# PIC32MX250F128B.net
KiCad netlist of a schematic drawn in EAGLE
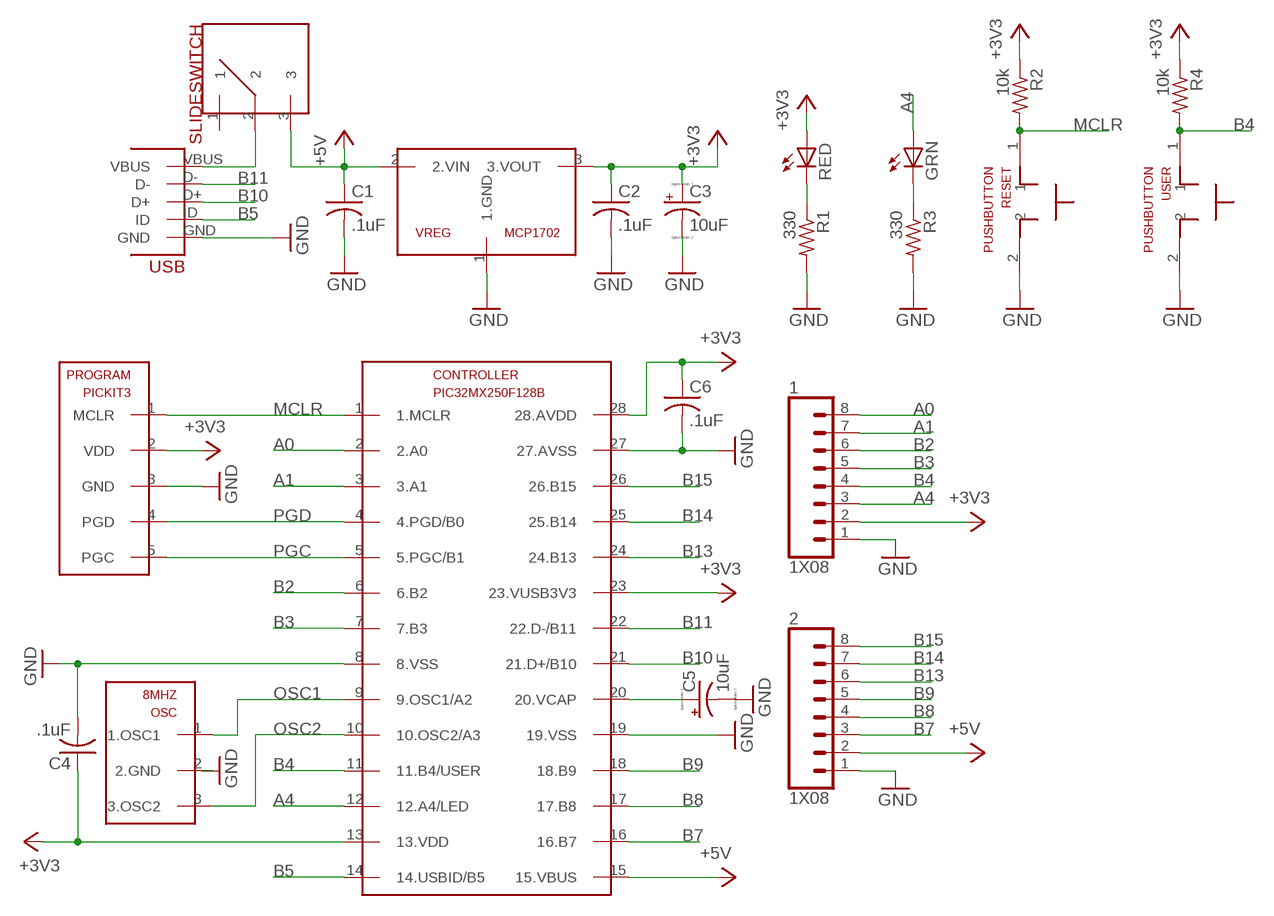
[diagram p0: schematic, sheet 1]

(export (version "E")
  (design (tool "Eeschema 10.0.6"))
  (components
    (comp (ref "1")
      (value "1X08")
      (footprint "eagle-import:CONN_08")
      (libsource (lib "eagle-import") (part "1X08"))
    )
    (comp (ref "2")
      (value "1X08")
      (footprint "eagle-import:CONN_08")
      (libsource (lib "eagle-import") (part "1X08"))
    )
    (comp (ref "8MHZ")
      (value "OSC")
      (footprint "eagle-import:OSC")
      (libsource (lib "eagle-import") (part "OSC"))
    )
    (comp (ref "C1")
      (value ".1uF")
      (footprint "eagle-import:C025-025X050")
      (libsource (lib "eagle-import") (part "C-US025-025X050"))
    )
    (comp (ref "C2")
      (value ".1uF")
      (footprint "eagle-import:C025-025X050")
      (libsource (lib "eagle-import") (part "C-US025-025X050"))
    )
    (comp (ref "C3")
      (value "10uF")
      (footprint "eagle-import:B45181B")
      (libsource (lib "eagle-import") (part "CPOL-USB45181B"))
    )
    (comp (ref "C4")
      (value ".1uF")
      (footprint "eagle-import:C025-025X050")
      (libsource (lib "eagle-import") (part "C-US025-025X050"))
    )
    (comp (ref "C5")
      (value "10uF")
      (footprint "eagle-import:B45181B")
      (libsource (lib "eagle-import") (part "CPOL-USB45181B"))
    )
    (comp (ref "C6")
      (value ".1uF")
      (footprint "eagle-import:C025-025X050")
      (libsource (lib "eagle-import") (part "C-US025-025X050"))
    )
    (comp (ref "CONTROLLER")
      (value "PIC32MX250F128B")
      (footprint "eagle-import:DIL28-3")
      (libsource (lib "eagle-import") (part "PIC32MX250F128B"))
    )
    (comp (ref "GRN")
      (value "LED3MM")
      (footprint "eagle-import:LED3MM")
      (libsource (lib "eagle-import") (part "LED3MM"))
    )
    (comp (ref "PROGRAM")
      (value "PICKIT3")
      (footprint "eagle-import:PICKIT3")
      (libsource (lib "eagle-import") (part "PICKIT3"))
    )
    (comp (ref "R1")
      (value "330")
      (footprint "eagle-import:0207_10")
      (libsource (lib "eagle-import") (part "R-US_0207/10"))
    )
    (comp (ref "R2")
      (value "10k")
      (footprint "eagle-import:0207_10")
      (libsource (lib "eagle-import") (part "R-US_0207/10"))
    )
    (comp (ref "R3")
      (value "330")
      (footprint "eagle-import:0207_10")
      (libsource (lib "eagle-import") (part "R-US_0207/10"))
    )
    (comp (ref "R4")
      (value "10k")
      (footprint "eagle-import:0207_10")
      (libsource (lib "eagle-import") (part "R-US_0207/10"))
    )
    (comp (ref "RED")
      (value "LED3MM")
      (footprint "eagle-import:LED3MM")
      (libsource (lib "eagle-import") (part "LED3MM"))
    )
    (comp (ref "RESET")
      (value "PUSHBUTTON")
      (footprint "eagle-import:PUSHBUTTON")
      (libsource (lib "eagle-import") (part "PUSHBUTTON"))
    )
    (comp (ref "SLIDESWITCH")
      (value "SLIDESWITCH")
      (footprint "eagle-import:SLIDESWITCH")
      (libsource (lib "eagle-import") (part "SLIDESWITCH"))
    )
    (comp (ref "USB")
      (value "MINIUSB")
      (footprint "eagle-import:USB-MB-H")
      (libsource (lib "eagle-import") (part "MINIUSB"))
    )
    (comp (ref "USER")
      (value "PUSHBUTTON")
      (footprint "eagle-import:PUSHBUTTON")
      (libsource (lib "eagle-import") (part "PUSHBUTTON"))
    )
    (comp (ref "VREG")
      (value "MCP1702")
      (footprint "eagle-import:TO92")
      (libsource (lib "eagle-import") (part "MCP1702"))
    )
  )
  (nets
    (net (code "1") (name "+3V3") (class "Default")
      (node (ref "1") (pin "2") (pinfunction "2_2") (pintype "passive"))
      (node (ref "C2") (pin "1") (pinfunction "1_1") (pintype "passive"))
      (node (ref "C3") (pin "+") (pinfunction "+_+") (pintype "passive"))
      (node (ref "C4") (pin "1") (pinfunction "1_1") (pintype "passive"))
      (node (ref "C6") (pin "1") (pinfunction "1_1") (pintype "passive"))
      (node (ref "CONTROLLER") (pin "13") (pinfunction "13.VDD_13") (pintype "bidirectional"))
      (node (ref "CONTROLLER") (pin "23") (pinfunction "23.VUSB3V3_23") (pintype "bidirectional"))
      (node (ref "CONTROLLER") (pin "28") (pinfunction "28.AVDD_28") (pintype "bidirectional"))
      (node (ref "PROGRAM") (pin "2") (pinfunction "VDD_2") (pintype "bidirectional"))
      (node (ref "R2") (pin "1") (pinfunction "1_1") (pintype "passive"))
      (node (ref "R4") (pin "1") (pinfunction "1_1") (pintype "passive"))
      (node (ref "RED") (pin "A") (pinfunction "A_A") (pintype "passive"))
      (node (ref "VREG") (pin "3") (pinfunction "3.VOUT_3") (pintype "bidirectional"))
    )
    (net (code "2") (name "+5V") (class "Default")
      (node (ref "2") (pin "2") (pinfunction "2_2") (pintype "passive"))
      (node (ref "C1") (pin "1") (pinfunction "1_1") (pintype "passive"))
      (node (ref "CONTROLLER") (pin "15") (pinfunction "15.VBUS_15") (pintype "bidirectional"))
      (node (ref "SLIDESWITCH") (pin "3") (pinfunction "3_3") (pintype "bidirectional"))
      (node (ref "VREG") (pin "2") (pinfunction "2.VIN_2") (pintype "bidirectional"))
    )
    (net (code "3") (name "/A0") (class "Default")
      (node (ref "1") (pin "8") (pinfunction "8_8") (pintype "passive"))
      (node (ref "CONTROLLER") (pin "2") (pinfunction "2.A0_2") (pintype "bidirectional"))
    )
    (net (code "4") (name "/A1") (class "Default")
      (node (ref "1") (pin "7") (pinfunction "7_7") (pintype "passive"))
      (node (ref "CONTROLLER") (pin "3") (pinfunction "3.A1_3") (pintype "bidirectional"))
    )
    (net (code "5") (name "/A4") (class "Default")
      (node (ref "1") (pin "3") (pinfunction "3_3") (pintype "passive"))
      (node (ref "CONTROLLER") (pin "12") (pinfunction "12.A4/LED_12") (pintype "bidirectional"))
      (node (ref "GRN") (pin "A") (pinfunction "A_A") (pintype "passive"))
    )
    (net (code "6") (name "/B2") (class "Default")
      (node (ref "1") (pin "6") (pinfunction "6_6") (pintype "passive"))
      (node (ref "CONTROLLER") (pin "6") (pinfunction "6.B2_6") (pintype "bidirectional"))
    )
    (net (code "7") (name "/B3") (class "Default")
      (node (ref "1") (pin "5") (pinfunction "5_5") (pintype "passive"))
      (node (ref "CONTROLLER") (pin "7") (pinfunction "7.B3_7") (pintype "bidirectional"))
    )
    (net (code "8") (name "/B4") (class "Default")
      (node (ref "1") (pin "4") (pinfunction "4_4") (pintype "passive"))
      (node (ref "CONTROLLER") (pin "11") (pinfunction "11.B4/USER_11") (pintype "bidirectional"))
      (node (ref "R4") (pin "2") (pinfunction "2_2") (pintype "passive"))
      (node (ref "USER") (pin "1") (pinfunction "1_1") (pintype "bidirectional"))
    )
    (net (code "9") (name "/B5") (class "Default")
      (node (ref "CONTROLLER") (pin "14") (pinfunction "14.USBID/B5_14") (pintype "bidirectional"))
      (node (ref "USB") (pin "ID") (pinfunction "ID_ID") (pintype "bidirectional"))
    )
    (net (code "10") (name "/B7") (class "Default")
      (node (ref "2") (pin "3") (pinfunction "3_3") (pintype "passive"))
      (node (ref "CONTROLLER") (pin "16") (pinfunction "16.B7_16") (pintype "bidirectional"))
    )
    (net (code "11") (name "/B8") (class "Default")
      (node (ref "2") (pin "4") (pinfunction "4_4") (pintype "passive"))
      (node (ref "CONTROLLER") (pin "17") (pinfunction "17.B8_17") (pintype "bidirectional"))
    )
    (net (code "12") (name "/B9") (class "Default")
      (node (ref "2") (pin "5") (pinfunction "5_5") (pintype "passive"))
      (node (ref "CONTROLLER") (pin "18") (pinfunction "18.B9_18") (pintype "bidirectional"))
    )
    (net (code "13") (name "/B10") (class "Default")
      (node (ref "CONTROLLER") (pin "21") (pinfunction "21.D+/B10_21") (pintype "bidirectional"))
      (node (ref "USB") (pin "D+") (pinfunction "D+_D+") (pintype "bidirectional"))
    )
    (net (code "14") (name "/B11") (class "Default")
      (node (ref "CONTROLLER") (pin "22") (pinfunction "22.D-/B11_22") (pintype "bidirectional"))
      (node (ref "USB") (pin "D-") (pinfunction "D-_D-") (pintype "bidirectional"))
    )
    (net (code "15") (name "/B13") (class "Default")
      (node (ref "2") (pin "6") (pinfunction "6_6") (pintype "passive"))
      (node (ref "CONTROLLER") (pin "24") (pinfunction "24.B13_24") (pintype "bidirectional"))
    )
    (net (code "16") (name "/B14") (class "Default")
      (node (ref "2") (pin "7") (pinfunction "7_7") (pintype "passive"))
      (node (ref "CONTROLLER") (pin "25") (pinfunction "25.B14_25") (pintype "bidirectional"))
    )
    (net (code "17") (name "/B15") (class "Default")
      (node (ref "2") (pin "8") (pinfunction "8_8") (pintype "passive"))
      (node (ref "CONTROLLER") (pin "26") (pinfunction "26.B15_26") (pintype "bidirectional"))
    )
    (net (code "18") (name "/MCLR") (class "Default")
      (node (ref "CONTROLLER") (pin "1") (pinfunction "1.MCLR_1") (pintype "bidirectional"))
      (node (ref "PROGRAM") (pin "1") (pinfunction "MCLR_1") (pintype "bidirectional"))
      (node (ref "R2") (pin "2") (pinfunction "2_2") (pintype "passive"))
      (node (ref "RESET") (pin "1") (pinfunction "1_1") (pintype "bidirectional"))
    )
    (net (code "19") (name "/OSC1") (class "Default")
      (node (ref "8MHZ") (pin "1") (pinfunction "1.OSC1_1") (pintype "bidirectional"))
      (node (ref "CONTROLLER") (pin "9") (pinfunction "9.OSC1/A2_9") (pintype "bidirectional"))
    )
    (net (code "20") (name "/OSC2") (class "Default")
      (node (ref "8MHZ") (pin "3") (pinfunction "3.OSC2_3") (pintype "bidirectional"))
      (node (ref "CONTROLLER") (pin "10") (pinfunction "10.OSC2/A3_10") (pintype "bidirectional"))
    )
    (net (code "21") (name "/PGC") (class "Default")
      (node (ref "CONTROLLER") (pin "5") (pinfunction "5.PGC/B1_5") (pintype "bidirectional"))
      (node (ref "PROGRAM") (pin "5") (pinfunction "PGC_5") (pintype "bidirectional"))
    )
    (net (code "22") (name "/PGD") (class "Default")
      (node (ref "CONTROLLER") (pin "4") (pinfunction "4.PGD/B0_4") (pintype "bidirectional"))
      (node (ref "PROGRAM") (pin "4") (pinfunction "PGD_4") (pintype "bidirectional"))
    )
    (net (code "23") (name "GND") (class "Default")
      (node (ref "1") (pin "1") (pinfunction "1_1") (pintype "passive"))
      (node (ref "2") (pin "1") (pinfunction "1_1") (pintype "passive"))
      (node (ref "8MHZ") (pin "2") (pinfunction "2.GND_2") (pintype "bidirectional"))
      (node (ref "C1") (pin "2") (pinfunction "2_2") (pintype "passive"))
      (node (ref "C2") (pin "2") (pinfunction "2_2") (pintype "passive"))
      (node (ref "C3") (pin "-") (pinfunction "-_-") (pintype "passive"))
      (node (ref "C4") (pin "2") (pinfunction "2_2") (pintype "passive"))
      (node (ref "C5") (pin "-") (pinfunction "-_-") (pintype "passive"))
      (node (ref "C6") (pin "2") (pinfunction "2_2") (pintype "passive"))
      (node (ref "CONTROLLER") (pin "19") (pinfunction "19.VSS_19") (pintype "bidirectional"))
      (node (ref "CONTROLLER") (pin "27") (pinfunction "27.AVSS_27") (pintype "bidirectional"))
      (node (ref "CONTROLLER") (pin "8") (pinfunction "8.VSS_8") (pintype "bidirectional"))
      (node (ref "PROGRAM") (pin "3") (pinfunction "GND_3") (pintype "bidirectional"))
      (node (ref "R1") (pin "2") (pinfunction "2_2") (pintype "passive"))
      (node (ref "R3") (pin "2") (pinfunction "2_2") (pintype "passive"))
      (node (ref "RESET") (pin "2") (pinfunction "2_2") (pintype "bidirectional"))
      (node (ref "USB") (pin "GND") (pinfunction "GND_GND") (pintype "bidirectional"))
      (node (ref "USER") (pin "2") (pinfunction "2_2") (pintype "bidirectional"))
      (node (ref "VREG") (pin "1") (pinfunction "1.GND_1") (pintype "bidirectional"))
    )
    (net (code "24") (name "Net-(CONTROLLER-20.VCAP)") (class "Default")
      (node (ref "C5") (pin "+") (pinfunction "+_+") (pintype "passive"))
      (node (ref "CONTROLLER") (pin "20") (pinfunction "20.VCAP_20") (pintype "bidirectional"))
    )
    (net (code "25") (name "Net-(GRN-C)") (class "Default")
      (node (ref "GRN") (pin "K") (pinfunction "C_K") (pintype "passive"))
      (node (ref "R3") (pin "1") (pinfunction "1_1") (pintype "passive"))
    )
    (net (code "26") (name "Net-(RED-C)") (class "Default")
      (node (ref "R1") (pin "1") (pinfunction "1_1") (pintype "passive"))
      (node (ref "RED") (pin "K") (pinfunction "C_K") (pintype "passive"))
    )
    (net (code "27") (name "Net-(SLIDESWITCH-Pad2)") (class "Default")
      (node (ref "SLIDESWITCH") (pin "2") (pinfunction "2_2") (pintype "bidirectional"))
      (node (ref "USB") (pin "VBUS") (pinfunction "VBUS_VBUS") (pintype "bidirectional"))
    )
    (net (code "28") (name "unconnected-(SLIDESWITCH-Pad1)") (class "Default")
      (node (ref "SLIDESWITCH") (pin "1") (pinfunction "1_1") (pintype "bidirectional"))
    )
  )
)
